# Arduino_Pro_Micro_Stepper_Shield.net
KiCad netlist of a schematic drawn in EasyEDA
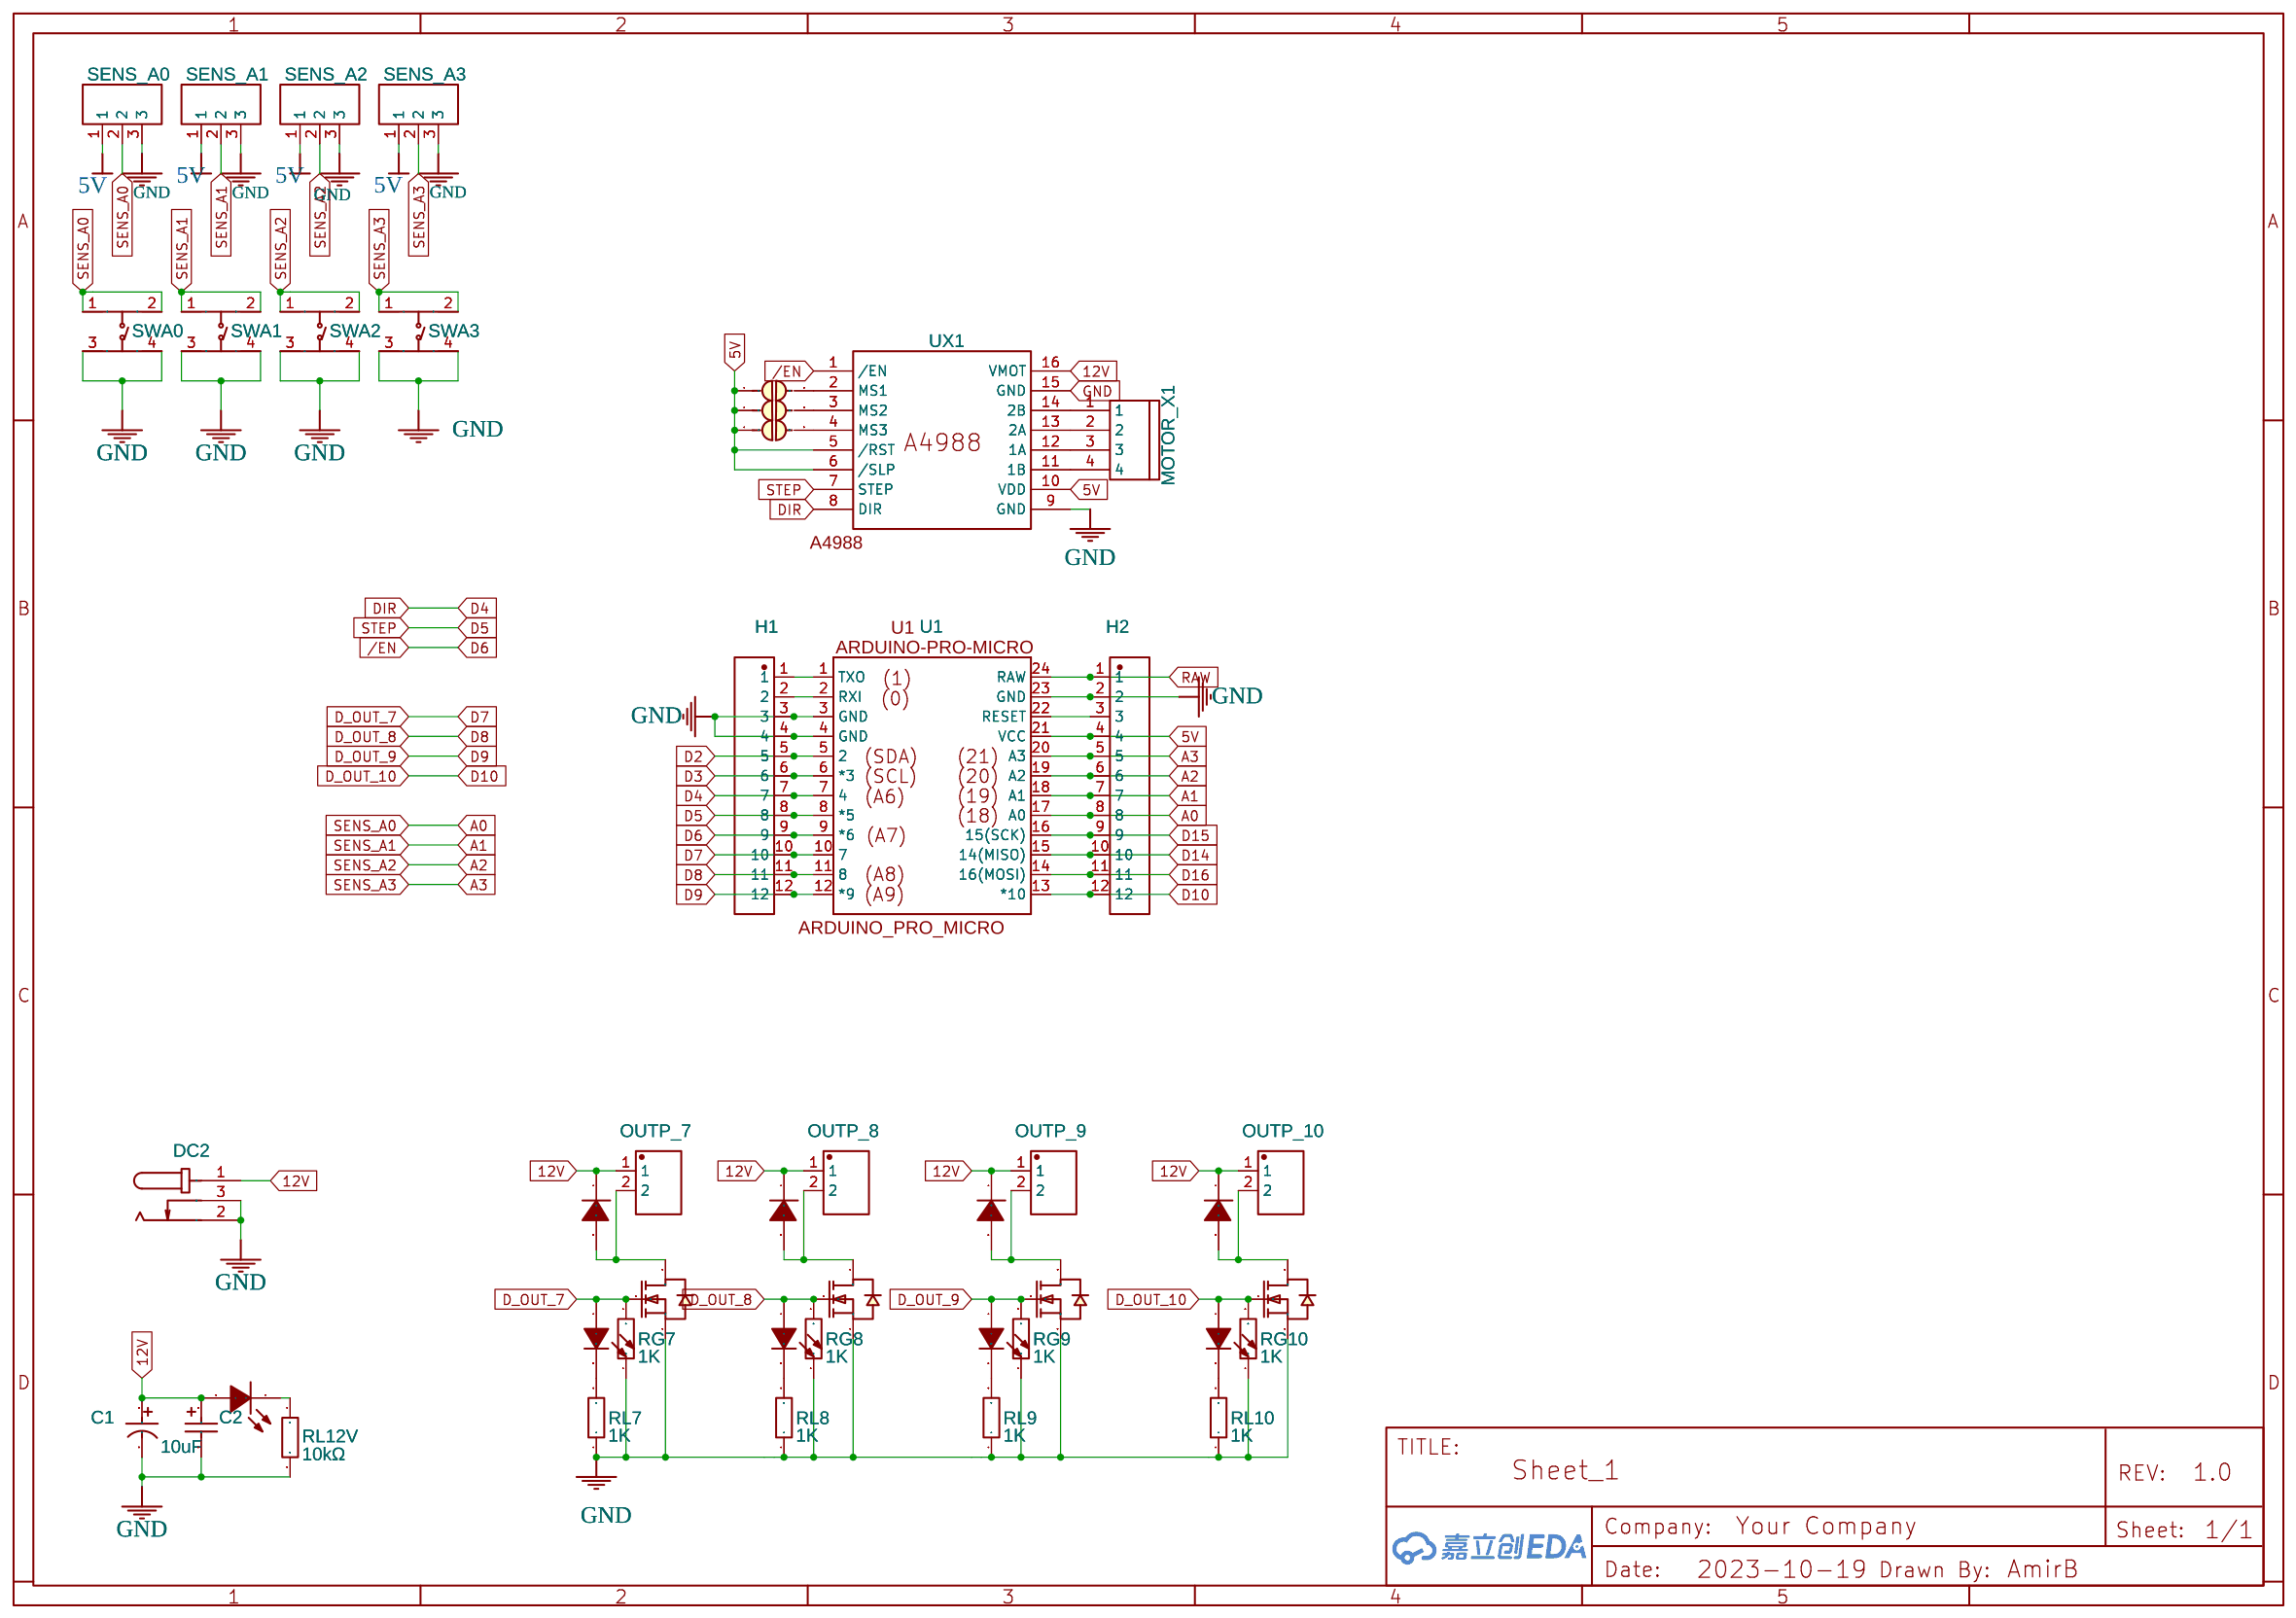
[diagram p0: schematic sheet]

(export (version "E")
  (design (tool "Eeschema 10.0.6"))
  (components
    (comp (ref "C1")
      (value "470uF")
      (fields
        (field (name "Manufacturer Part") "GR477M025F12RR0VH4FP0")
        (field (name "Manufacturer") "CX(承兴)")
      )
      (libsource (lib "") (part "470uF 25V 8*12Black high frequency"))
    )
    (comp (ref "C2")
      (value "10uF")
      (fields (field (name "Manufacturer Part") "TAJA106K016RNJ") (field (name "Manufacturer") "Kyocera AVX"))
      (libsource (lib "") (part "TAJA106K016RNJ"))
    )
    (comp (ref "DC2")
      (value "DC")
      (fields
        (field (name "BOM_Manufacturer Part") "DC005-2.0MM")
        (field (name "BOM_Supplier Part") "C111567")
      )
      (libsource (lib "") (part "DC005-2.0MM"))
    )
    (comp (ref "DOUT7")
      (value "1N4007")
      (fields (field (name "BOM_Manufacturer Part") "1N4007F") (field (name "BOM_Supplier Part") "C110856"))
      (libsource (lib "") (part "1N4007F"))
    )
    (comp (ref "DOUT8")
      (value "1N4007")
      (fields (field (name "BOM_Manufacturer Part") "1N4007F") (field (name "BOM_Supplier Part") "C110856"))
      (libsource (lib "") (part "1N4007F"))
    )
    (comp (ref "DOUT9")
      (value "1N4007")
      (fields (field (name "BOM_Manufacturer Part") "1N4007F") (field (name "BOM_Supplier Part") "C110856"))
      (libsource (lib "") (part "1N4007F"))
    )
    (comp (ref "DOUT10")
      (value "1N4007")
      (fields (field (name "BOM_Manufacturer Part") "1N4007F") (field (name "BOM_Supplier Part") "C110856"))
      (libsource (lib "") (part "1N4007F"))
    )
    (comp (ref "DQ7")
      (value "Q")
      (fields (field (name "BOM_Manufacturer Part") "AO3400") (field (name "BOM_Supplier Part") "C5224189"))
      (libsource (lib "") (part "JSM2302"))
    )
    (comp (ref "DQ8")
      (value "Q")
      (fields (field (name "BOM_Manufacturer Part") "AO3400") (field (name "BOM_Supplier Part") "C5224189"))
      (libsource (lib "") (part "JSM2302"))
    )
    (comp (ref "DQ9")
      (value "Q")
      (fields (field (name "BOM_Manufacturer Part") "AO3400") (field (name "BOM_Supplier Part") "C5224189"))
      (libsource (lib "") (part "JSM2302"))
    )
    (comp (ref "DQ10")
      (value "Q")
      (fields (field (name "BOM_Manufacturer Part") "AO3400") (field (name "BOM_Supplier Part") "C5224189"))
      (libsource (lib "") (part "JSM2302"))
    )
    (comp (ref "H1")
      (value "KH-2.54PH180-1X12P-L11.5")
      (fields (field (name "Manufacturer") "kinghelm(金航标)"))
      (libsource (lib "") (part "KH-2.54PH180-1X12P-L11.5"))
    )
    (comp (ref "H2")
      (value "KH-2.54PH180-1X12P-L11.5")
      (fields (field (name "Manufacturer") "kinghelm(金航标)"))
      (libsource (lib "") (part "KH-2.54PH180-1X12P-L11.5_1"))
    )
    (comp (ref "JX1") (value "JUMPER-SMT_2") (libsource (lib "") (part "JUMPER-SMT_2")))
    (comp (ref "JX2") (value "JUMPER-SMT_2") (libsource (lib "") (part "JUMPER-SMT_2")))
    (comp (ref "JX3") (value "JUMPER-SMT_2") (libsource (lib "") (part "JUMPER-SMT_2")))
    (comp (ref "LD7")
      (value "LED")
      (fields
        (field (name "BOM_Manufacturer Part") "19-217/BHC-ZL1M2RY/3T")
        (field (name "BOM_Supplier Part") "C72041")
      )
      (libsource (lib "") (part "19-217/BHC-ZL1M2RY/3T"))
    )
    (comp (ref "LD8")
      (value "LED")
      (fields
        (field (name "BOM_Manufacturer Part") "19-217/BHC-ZL1M2RY/3T")
        (field (name "BOM_Supplier Part") "C72041")
      )
      (libsource (lib "") (part "19-217/BHC-ZL1M2RY/3T"))
    )
    (comp (ref "LD9")
      (value "LED")
      (fields
        (field (name "BOM_Manufacturer Part") "19-217/BHC-ZL1M2RY/3T")
        (field (name "BOM_Supplier Part") "C72041")
      )
      (libsource (lib "") (part "19-217/BHC-ZL1M2RY/3T"))
    )
    (comp (ref "LD10")
      (value "LED")
      (fields
        (field (name "BOM_Manufacturer Part") "19-217/BHC-ZL1M2RY/3T")
        (field (name "BOM_Supplier Part") "C72041")
      )
      (libsource (lib "") (part "19-217/BHC-ZL1M2RY/3T"))
    )
    (comp (ref "LED1")
      (value "KT-0603R")
      (fields (field (name "Manufacturer") "KENTO"))
      (libsource (lib "") (part "KT-0603R"))
    )
    (comp (ref "MOTOR_X1")
      (value "XH2.54-4AW")
      (fields (field (name "Manufacturer Part") "XH-4AW") (field (name "Manufacturer") "BOOMELE(博穆精密)"))
      (libsource (lib "") (part "XH2.54-4AW"))
    )
    (comp (ref "OUTP_7")
      (value "KF2510-2A")
      (fields (field (name "BOM_Supplier Part") "C27543"))
      (libsource (lib "") (part "KF2510-2A"))
    )
    (comp (ref "OUTP_8")
      (value "KF2510-2A")
      (fields (field (name "BOM_Supplier Part") "C27543"))
      (libsource (lib "") (part "KF2510-2A"))
    )
    (comp (ref "OUTP_9")
      (value "KF2510-2A")
      (fields (field (name "BOM_Supplier Part") "C27543"))
      (libsource (lib "") (part "KF2510-2A"))
    )
    (comp (ref "OUTP_10")
      (value "KF2510-2A")
      (fields (field (name "BOM_Supplier Part") "C27543"))
      (libsource (lib "") (part "KF2510-2A"))
    )
    (comp (ref "RG7")
      (value "1K")
      (fields
        (field (name "BOM_Manufacturer Part") "0603WAF1001T5E")
        (field (name "BOM_Supplier Part") "C21190")
      )
      (libsource (lib "") (part "0603WAF1001T5E"))
    )
    (comp (ref "RG8")
      (value "1K")
      (fields
        (field (name "BOM_Manufacturer Part") "0603WAF1001T5E")
        (field (name "BOM_Supplier Part") "C21190")
      )
      (libsource (lib "") (part "0603WAF1001T5E"))
    )
    (comp (ref "RG9")
      (value "1K")
      (fields
        (field (name "BOM_Manufacturer Part") "0603WAF1001T5E")
        (field (name "BOM_Supplier Part") "C21190")
      )
      (libsource (lib "") (part "0603WAF1001T5E"))
    )
    (comp (ref "RG10")
      (value "1K")
      (fields
        (field (name "BOM_Manufacturer Part") "0603WAF1001T5E")
        (field (name "BOM_Supplier Part") "C21190")
      )
      (libsource (lib "") (part "0603WAF1001T5E"))
    )
    (comp (ref "RL7")
      (value "1K")
      (fields
        (field (name "BOM_Manufacturer Part") "0603WAF1001T5E")
        (field (name "BOM_Supplier Part") "C21190")
      )
      (libsource (lib "") (part "0603WAF1001T5E_1"))
    )
    (comp (ref "RL8")
      (value "1K")
      (fields
        (field (name "BOM_Manufacturer Part") "0603WAF1001T5E")
        (field (name "BOM_Supplier Part") "C21190")
      )
      (libsource (lib "") (part "0603WAF1001T5E_1"))
    )
    (comp (ref "RL9")
      (value "1K")
      (fields
        (field (name "BOM_Manufacturer Part") "0603WAF1001T5E")
        (field (name "BOM_Supplier Part") "C21190")
      )
      (libsource (lib "") (part "0603WAF1001T5E_1"))
    )
    (comp (ref "RL10")
      (value "1K")
      (fields
        (field (name "BOM_Manufacturer Part") "0603WAF1001T5E")
        (field (name "BOM_Supplier Part") "C21190")
      )
      (libsource (lib "") (part "0603WAF1001T5E_1"))
    )
    (comp (ref "RL12V")
      (value "10kΩ")
      (fields
        (field (name "BOM_Manufacturer Part") "0603WAF1002T5E")
        (field (name "BOM_Supplier Part") "C25804")
      )
      (libsource (lib "") (part "0603WAF1002T5E"))
    )
    (comp (ref "SENS_A0")
      (value "FK2510")
      (fields (field (name "Manufacturer Part") "2510-3A") (field (name "Manufacturer") "BOOMELE(博穆精密)"))
      (libsource (lib "") (part "kf2510_3A"))
    )
    (comp (ref "SENS_A1")
      (value "FK2510")
      (fields (field (name "Manufacturer Part") "2510-3A") (field (name "Manufacturer") "BOOMELE(博穆精密)"))
      (libsource (lib "") (part "kf2510_3A"))
    )
    (comp (ref "SENS_A2")
      (value "FK2510")
      (fields (field (name "Manufacturer Part") "2510-3A") (field (name "Manufacturer") "BOOMELE(博穆精密)"))
      (libsource (lib "") (part "kf2510_3A"))
    )
    (comp (ref "SENS_A3")
      (value "FK2510")
      (fields (field (name "Manufacturer Part") "2510-3A") (field (name "Manufacturer") "BOOMELE(博穆精密)"))
      (libsource (lib "") (part "kf2510_3A"))
    )
    (comp (ref "SWA0")
      (value "TC-6610-7-160G")
      (fields (field (name "Manufacturer") "HCTL(华灿天禄)"))
      (libsource (lib "") (part "TC-6610-7-160G"))
    )
    (comp (ref "SWA1")
      (value "TC-6610-7-160G")
      (fields (field (name "Manufacturer") "HCTL(华灿天禄)"))
      (libsource (lib "") (part "TC-6610-7-160G"))
    )
    (comp (ref "SWA2")
      (value "TC-6610-7-160G")
      (fields (field (name "Manufacturer") "HCTL(华灿天禄)"))
      (libsource (lib "") (part "TC-6610-7-160G"))
    )
    (comp (ref "SWA3")
      (value "TC-6610-7-160G")
      (fields (field (name "Manufacturer") "HCTL(华灿天禄)"))
      (libsource (lib "") (part "TC-6610-7-160G"))
    )
    (comp (ref "U1") (value "ARDUINO-PRO-MICRO") (libsource (lib "") (part "ARDUINO-PRO-MICRO")))
    (comp (ref "UX1") (value "A4988") (libsource (lib "") (part "A4988")))
  )
  (nets
    (net (code "1") (name "5V") (class "Default")
      (node (ref "H2") (pin "4") (pinfunction "4_4") (pintype "unspecified"))
      (node (ref "JX1") (pin "1") (pinfunction "1_1") (pintype "bidirectional"))
      (node (ref "JX2") (pin "1") (pinfunction "1_1") (pintype "bidirectional"))
      (node (ref "JX3") (pin "1") (pinfunction "1_1") (pintype "bidirectional"))
      (node (ref "SENS_A0") (pin "1") (pinfunction "1_1") (pintype "unspecified"))
      (node (ref "SENS_A1") (pin "1") (pinfunction "1_1") (pintype "unspecified"))
      (node (ref "SENS_A2") (pin "1") (pinfunction "1_1") (pintype "unspecified"))
      (node (ref "SENS_A3") (pin "1") (pinfunction "1_1") (pintype "unspecified"))
      (node (ref "U1") (pin "21") (pinfunction "VCC_21") (pintype "unspecified"))
      (node (ref "UX1") (pin "10") (pinfunction "VDD_10") (pintype "unspecified"))
      (node (ref "UX1") (pin "5") (pinfunction "/RST_5") (pintype "unspecified"))
      (node (ref "UX1") (pin "6") (pinfunction "/SLP_6") (pintype "unspecified"))
    )
    (net (code "2") (name "12V") (class "Default")
      (node (ref "C1") (pin "1") (pinfunction "1_1") (pintype "input"))
      (node (ref "C2") (pin "1") (pinfunction "1_1") (pintype "input"))
      (node (ref "DC2") (pin "1") (pinfunction "1_1") (pintype "unspecified"))
      (node (ref "DOUT10") (pin "1") (pinfunction "C_1") (pintype "unspecified"))
      (node (ref "DOUT7") (pin "1") (pinfunction "C_1") (pintype "unspecified"))
      (node (ref "DOUT8") (pin "1") (pinfunction "C_1") (pintype "unspecified"))
      (node (ref "DOUT9") (pin "1") (pinfunction "C_1") (pintype "unspecified"))
      (node (ref "LED1") (pin "2") (pinfunction "A_2") (pintype "unspecified"))
      (node (ref "OUTP_10") (pin "1") (pinfunction "1_1") (pintype "unspecified"))
      (node (ref "OUTP_7") (pin "1") (pinfunction "1_1") (pintype "unspecified"))
      (node (ref "OUTP_8") (pin "1") (pinfunction "1_1") (pintype "unspecified"))
      (node (ref "OUTP_9") (pin "1") (pinfunction "1_1") (pintype "unspecified"))
      (node (ref "UX1") (pin "16") (pinfunction "VMOT_16") (pintype "unspecified"))
    )
    (net (code "3") (name "A0") (class "Default")
      (node (ref "H2") (pin "8") (pinfunction "8_8") (pintype "unspecified"))
      (node (ref "SENS_A0") (pin "2") (pinfunction "2_2") (pintype "unspecified"))
      (node (ref "SWA0") (pin "1") (pinfunction "1_1") (pintype "unspecified"))
      (node (ref "SWA0") (pin "2") (pinfunction "2_2") (pintype "unspecified"))
      (node (ref "U1") (pin "17") (pinfunction "A0_17") (pintype "unspecified"))
    )
    (net (code "4") (name "A1") (class "Default")
      (node (ref "H2") (pin "7") (pinfunction "7_7") (pintype "unspecified"))
      (node (ref "SENS_A1") (pin "2") (pinfunction "2_2") (pintype "unspecified"))
      (node (ref "SWA1") (pin "1") (pinfunction "1_1") (pintype "unspecified"))
      (node (ref "SWA1") (pin "2") (pinfunction "2_2") (pintype "unspecified"))
      (node (ref "U1") (pin "18") (pinfunction "A1_18") (pintype "unspecified"))
    )
    (net (code "5") (name "A2") (class "Default")
      (node (ref "H2") (pin "6") (pinfunction "6_6") (pintype "unspecified"))
      (node (ref "SENS_A2") (pin "2") (pinfunction "2_2") (pintype "unspecified"))
      (node (ref "SWA2") (pin "1") (pinfunction "1_1") (pintype "unspecified"))
      (node (ref "SWA2") (pin "2") (pinfunction "2_2") (pintype "unspecified"))
      (node (ref "U1") (pin "19") (pinfunction "A2_19") (pintype "unspecified"))
    )
    (net (code "6") (name "A3") (class "Default")
      (node (ref "H2") (pin "5") (pinfunction "5_5") (pintype "unspecified"))
      (node (ref "SENS_A3") (pin "2") (pinfunction "2_2") (pintype "unspecified"))
      (node (ref "SWA3") (pin "1") (pinfunction "1_1") (pintype "unspecified"))
      (node (ref "SWA3") (pin "2") (pinfunction "2_2") (pintype "unspecified"))
      (node (ref "U1") (pin "20") (pinfunction "A3_20") (pintype "unspecified"))
    )
    (net (code "7") (name "D2") (class "Default")
      (node (ref "H1") (pin "5") (pinfunction "5_5") (pintype "unspecified"))
      (node (ref "U1") (pin "5") (pinfunction "2_5") (pintype "unspecified"))
    )
    (net (code "8") (name "D3") (class "Default")
      (node (ref "H1") (pin "6") (pinfunction "6_6") (pintype "unspecified"))
      (node (ref "U1") (pin "6") (pinfunction "*3_6") (pintype "unspecified"))
    )
    (net (code "9") (name "D4") (class "Default")
      (node (ref "H1") (pin "7") (pinfunction "7_7") (pintype "unspecified"))
      (node (ref "U1") (pin "7") (pinfunction "4_7") (pintype "unspecified"))
      (node (ref "UX1") (pin "8") (pinfunction "DIR_8") (pintype "unspecified"))
    )
    (net (code "10") (name "D5") (class "Default")
      (node (ref "H1") (pin "8") (pinfunction "8_8") (pintype "unspecified"))
      (node (ref "U1") (pin "8") (pinfunction "*5_8") (pintype "unspecified"))
      (node (ref "UX1") (pin "7") (pinfunction "STEP_7") (pintype "unspecified"))
    )
    (net (code "11") (name "D6") (class "Default")
      (node (ref "H1") (pin "9") (pinfunction "9_9") (pintype "unspecified"))
      (node (ref "U1") (pin "9") (pinfunction "*6_9") (pintype "unspecified"))
      (node (ref "UX1") (pin "1") (pinfunction "/EN_1") (pintype "unspecified"))
    )
    (net (code "12") (name "D7") (class "Default")
      (node (ref "DQ7") (pin "1") (pinfunction "G_1") (pintype "unspecified"))
      (node (ref "H1") (pin "10") (pinfunction "10_10") (pintype "unspecified"))
      (node (ref "LD7") (pin "1") (pinfunction "A_1") (pintype "input"))
      (node (ref "RG7") (pin "2") (pinfunction "2_2") (pintype "input"))
      (node (ref "U1") (pin "10") (pinfunction "7_10") (pintype "unspecified"))
    )
    (net (code "13") (name "D8") (class "Default")
      (node (ref "DQ8") (pin "1") (pinfunction "G_1") (pintype "unspecified"))
      (node (ref "H1") (pin "11") (pinfunction "11_11") (pintype "unspecified"))
      (node (ref "LD8") (pin "1") (pinfunction "A_1") (pintype "input"))
      (node (ref "RG8") (pin "2") (pinfunction "2_2") (pintype "input"))
      (node (ref "U1") (pin "11") (pinfunction "8_11") (pintype "unspecified"))
    )
    (net (code "14") (name "D9") (class "Default")
      (node (ref "DQ9") (pin "1") (pinfunction "G_1") (pintype "unspecified"))
      (node (ref "H1") (pin "12") (pinfunction "12_12") (pintype "unspecified"))
      (node (ref "LD9") (pin "1") (pinfunction "A_1") (pintype "input"))
      (node (ref "RG9") (pin "2") (pinfunction "2_2") (pintype "input"))
      (node (ref "U1") (pin "12") (pinfunction "*9_12") (pintype "unspecified"))
    )
    (net (code "15") (name "D10") (class "Default")
      (node (ref "DQ10") (pin "1") (pinfunction "G_1") (pintype "unspecified"))
      (node (ref "H2") (pin "12") (pinfunction "12_12") (pintype "unspecified"))
      (node (ref "LD10") (pin "1") (pinfunction "A_1") (pintype "input"))
      (node (ref "RG10") (pin "2") (pinfunction "2_2") (pintype "input"))
      (node (ref "U1") (pin "13") (pinfunction "*10_13") (pintype "unspecified"))
    )
    (net (code "16") (name "D14") (class "Default")
      (node (ref "H2") (pin "10") (pinfunction "10_10") (pintype "unspecified"))
      (node (ref "U1") (pin "15") (pinfunction "14(MISO)_15") (pintype "unspecified"))
    )
    (net (code "17") (name "D15") (class "Default")
      (node (ref "H2") (pin "9") (pinfunction "9_9") (pintype "unspecified"))
      (node (ref "U1") (pin "16") (pinfunction "15(SCK)_16") (pintype "unspecified"))
    )
    (net (code "18") (name "D16") (class "Default")
      (node (ref "H2") (pin "11") (pinfunction "11_11") (pintype "unspecified"))
      (node (ref "U1") (pin "14") (pinfunction "16(MOSI)_14") (pintype "unspecified"))
    )
    (net (code "19") (name "GND") (class "Default")
      (node (ref "C1") (pin "2") (pinfunction "2_2") (pintype "input"))
      (node (ref "C2") (pin "2") (pinfunction "2_2") (pintype "input"))
      (node (ref "DC2") (pin "2") (pinfunction "2_2") (pintype "unspecified"))
      (node (ref "DC2") (pin "3") (pinfunction "3_3") (pintype "unspecified"))
      (node (ref "DQ10") (pin "2") (pinfunction "S_2") (pintype "unspecified"))
      (node (ref "DQ7") (pin "2") (pinfunction "S_2") (pintype "unspecified"))
      (node (ref "DQ8") (pin "2") (pinfunction "S_2") (pintype "unspecified"))
      (node (ref "DQ9") (pin "2") (pinfunction "S_2") (pintype "unspecified"))
      (node (ref "H1") (pin "3") (pinfunction "3_3") (pintype "unspecified"))
      (node (ref "H1") (pin "4") (pinfunction "4_4") (pintype "unspecified"))
      (node (ref "H2") (pin "2") (pinfunction "2_2") (pintype "unspecified"))
      (node (ref "RG10") (pin "1") (pinfunction "1_1") (pintype "input"))
      (node (ref "RG7") (pin "1") (pinfunction "1_1") (pintype "input"))
      (node (ref "RG8") (pin "1") (pinfunction "1_1") (pintype "input"))
      (node (ref "RG9") (pin "1") (pinfunction "1_1") (pintype "input"))
      (node (ref "RL10") (pin "1") (pinfunction "1_1") (pintype "input"))
      (node (ref "RL12V") (pin "2") (pinfunction "2_2") (pintype "input"))
      (node (ref "RL7") (pin "1") (pinfunction "1_1") (pintype "input"))
      (node (ref "RL8") (pin "1") (pinfunction "1_1") (pintype "input"))
      (node (ref "RL9") (pin "1") (pinfunction "1_1") (pintype "input"))
      (node (ref "SENS_A0") (pin "3") (pinfunction "3_3") (pintype "unspecified"))
      (node (ref "SENS_A1") (pin "3") (pinfunction "3_3") (pintype "unspecified"))
      (node (ref "SENS_A2") (pin "3") (pinfunction "3_3") (pintype "unspecified"))
      (node (ref "SENS_A3") (pin "3") (pinfunction "3_3") (pintype "unspecified"))
      (node (ref "SWA0") (pin "3") (pinfunction "3_3") (pintype "unspecified"))
      (node (ref "SWA0") (pin "4") (pinfunction "4_4") (pintype "unspecified"))
      (node (ref "SWA1") (pin "3") (pinfunction "3_3") (pintype "unspecified"))
      (node (ref "SWA1") (pin "4") (pinfunction "4_4") (pintype "unspecified"))
      (node (ref "SWA2") (pin "3") (pinfunction "3_3") (pintype "unspecified"))
      (node (ref "SWA2") (pin "4") (pinfunction "4_4") (pintype "unspecified"))
      (node (ref "SWA3") (pin "3") (pinfunction "3_3") (pintype "unspecified"))
      (node (ref "SWA3") (pin "4") (pinfunction "4_4") (pintype "unspecified"))
      (node (ref "U1") (pin "23") (pinfunction "GND_23") (pintype "unspecified"))
      (node (ref "U1") (pin "3") (pinfunction "GND_3") (pintype "unspecified"))
      (node (ref "U1") (pin "4") (pinfunction "GND_4") (pintype "unspecified"))
      (node (ref "UX1") (pin "15") (pinfunction "GND_15") (pintype "unspecified"))
      (node (ref "UX1") (pin "9") (pinfunction "GND_9") (pintype "unspecified"))
    )
    (net (code "20") (name "Net-(DOUT7-A)") (class "Default")
      (node (ref "DOUT7") (pin "2") (pinfunction "A_2") (pintype "unspecified"))
      (node (ref "DQ7") (pin "3") (pinfunction "D_3") (pintype "unspecified"))
      (node (ref "OUTP_7") (pin "2") (pinfunction "2_2") (pintype "unspecified"))
    )
    (net (code "21") (name "Net-(DOUT8-A)") (class "Default")
      (node (ref "DOUT8") (pin "2") (pinfunction "A_2") (pintype "unspecified"))
      (node (ref "DQ8") (pin "3") (pinfunction "D_3") (pintype "unspecified"))
      (node (ref "OUTP_8") (pin "2") (pinfunction "2_2") (pintype "unspecified"))
    )
    (net (code "22") (name "Net-(DOUT9-A)") (class "Default")
      (node (ref "DOUT9") (pin "2") (pinfunction "A_2") (pintype "unspecified"))
      (node (ref "DQ9") (pin "3") (pinfunction "D_3") (pintype "unspecified"))
      (node (ref "OUTP_9") (pin "2") (pinfunction "2_2") (pintype "unspecified"))
    )
    (net (code "23") (name "Net-(DOUT10-A)") (class "Default")
      (node (ref "DOUT10") (pin "2") (pinfunction "A_2") (pintype "unspecified"))
      (node (ref "DQ10") (pin "3") (pinfunction "D_3") (pintype "unspecified"))
      (node (ref "OUTP_10") (pin "2") (pinfunction "2_2") (pintype "unspecified"))
    )
    (net (code "24") (name "Net-(LD7-C)") (class "Default")
      (node (ref "LD7") (pin "2") (pinfunction "C_2") (pintype "input"))
      (node (ref "RL7") (pin "2") (pinfunction "2_2") (pintype "input"))
    )
    (net (code "25") (name "Net-(LD8-C)") (class "Default")
      (node (ref "LD8") (pin "2") (pinfunction "C_2") (pintype "input"))
      (node (ref "RL8") (pin "2") (pinfunction "2_2") (pintype "input"))
    )
    (net (code "26") (name "Net-(LD9-C)") (class "Default")
      (node (ref "LD9") (pin "2") (pinfunction "C_2") (pintype "input"))
      (node (ref "RL9") (pin "2") (pinfunction "2_2") (pintype "input"))
    )
    (net (code "27") (name "Net-(LD10-C)") (class "Default")
      (node (ref "LD10") (pin "2") (pinfunction "C_2") (pintype "input"))
      (node (ref "RL10") (pin "2") (pinfunction "2_2") (pintype "input"))
    )
    (net (code "28") (name "Net-(LED1-K)") (class "Default")
      (node (ref "LED1") (pin "1") (pinfunction "K_1") (pintype "unspecified"))
      (node (ref "RL12V") (pin "1") (pinfunction "1_1") (pintype "input"))
    )
    (net (code "29") (name "Net-(U1-RESET)") (class "Default")
      (node (ref "H2") (pin "3") (pinfunction "3_3") (pintype "unspecified"))
      (node (ref "U1") (pin "22") (pinfunction "RESET_22") (pintype "unspecified"))
    )
    (net (code "30") (name "Net-(U1-RXI)") (class "Default")
      (node (ref "H1") (pin "2") (pinfunction "2_2") (pintype "unspecified"))
      (node (ref "U1") (pin "2") (pinfunction "RXI_2") (pintype "unspecified"))
    )
    (net (code "31") (name "Net-(U1-TXO)") (class "Default")
      (node (ref "H1") (pin "1") (pinfunction "1_1") (pintype "unspecified"))
      (node (ref "U1") (pin "1") (pinfunction "TXO_1") (pintype "unspecified"))
    )
    (net (code "32") (name "Net-(UX1-1A)") (class "Default")
      (node (ref "MOTOR_X1") (pin "3") (pinfunction "3_3") (pintype "unspecified"))
      (node (ref "UX1") (pin "12") (pinfunction "1A_12") (pintype "unspecified"))
    )
    (net (code "33") (name "Net-(UX1-1B)") (class "Default")
      (node (ref "MOTOR_X1") (pin "4") (pinfunction "4_4") (pintype "unspecified"))
      (node (ref "UX1") (pin "11") (pinfunction "1B_11") (pintype "unspecified"))
    )
    (net (code "34") (name "Net-(UX1-2A)") (class "Default")
      (node (ref "MOTOR_X1") (pin "2") (pinfunction "2_2") (pintype "unspecified"))
      (node (ref "UX1") (pin "13") (pinfunction "2A_13") (pintype "unspecified"))
    )
    (net (code "35") (name "Net-(UX1-2B)") (class "Default")
      (node (ref "MOTOR_X1") (pin "1") (pinfunction "1_1") (pintype "unspecified"))
      (node (ref "UX1") (pin "14") (pinfunction "2B_14") (pintype "unspecified"))
    )
    (net (code "36") (name "Net-(UX1-MS1)") (class "Default")
      (node (ref "JX1") (pin "2") (pinfunction "2_2") (pintype "bidirectional"))
      (node (ref "UX1") (pin "2") (pinfunction "MS1_2") (pintype "unspecified"))
    )
    (net (code "37") (name "Net-(UX1-MS2)") (class "Default")
      (node (ref "JX2") (pin "2") (pinfunction "2_2") (pintype "bidirectional"))
      (node (ref "UX1") (pin "3") (pinfunction "MS2_3") (pintype "unspecified"))
    )
    (net (code "38") (name "Net-(UX1-MS3)") (class "Default")
      (node (ref "JX3") (pin "2") (pinfunction "2_2") (pintype "bidirectional"))
      (node (ref "UX1") (pin "4") (pinfunction "MS3_4") (pintype "unspecified"))
    )
    (net (code "39") (name "RAW") (class "Default")
      (node (ref "H2") (pin "1") (pinfunction "1_1") (pintype "unspecified"))
      (node (ref "U1") (pin "24") (pinfunction "RAW_24") (pintype "unspecified"))
    )
  )
)
